# HM10_Breakout.net
KiCad netlist of a schematic drawn in EAGLE
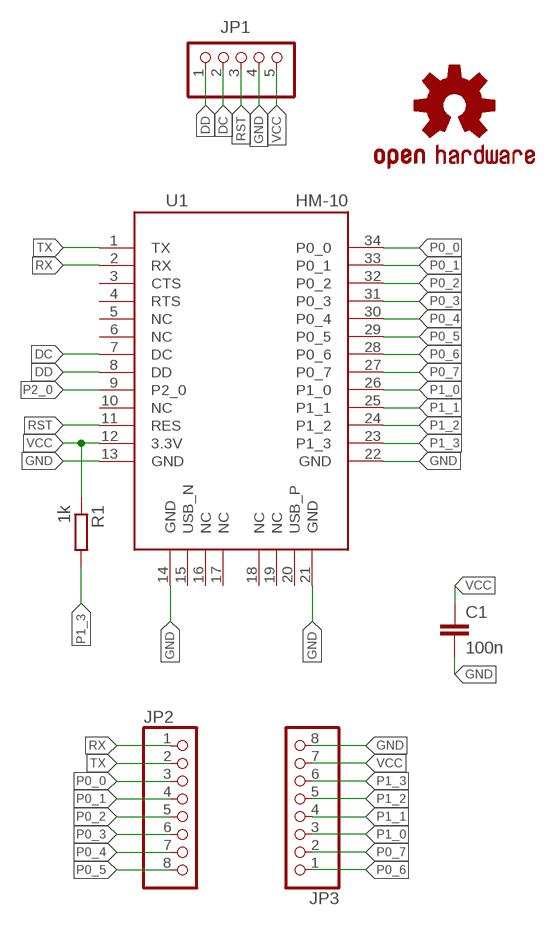
[diagram p0: schematic, sheet 1]

(export (version "E")
  (design (tool "Eeschema 10.0.6"))
  (components
    (comp (ref "C1")
      (value "100n")
      (footprint "eagle-import:1206")
      (libsource (lib "eagle-import") (part "C-EU1206"))
    )
    (comp (ref "JP1")
      (value "PINHD-1X5")
      (footprint "eagle-import:1X05")
      (libsource (lib "eagle-import") (part "PINHD-1X5"))
    )
    (comp (ref "JP2")
      (value "PINHD-1X8")
      (footprint "eagle-import:1X08")
      (libsource (lib "eagle-import") (part "PINHD-1X8"))
    )
    (comp (ref "JP3")
      (value "PINHD-1X8")
      (footprint "eagle-import:1X08")
      (libsource (lib "eagle-import") (part "PINHD-1X8"))
    )
    (comp (ref "LOGO1")
      (value "OSHW-LOGOM")
      (footprint "eagle-import:OSHW-LOGO-M")
      (libsource (lib "eagle-import") (part "OSHW-LOGOM"))
    )
    (comp (ref "R1")
      (value "1k")
      (footprint "eagle-import:R1206")
      (libsource (lib "eagle-import") (part "R-EU_R1206"))
    )
    (comp (ref "U1")
      (value "HM-10")
      (footprint "eagle-import:HM-10")
      (libsource (lib "eagle-import") (part "HM-10"))
    )
  )
  (nets
    (net (code "1") (name "DC") (class "Default")
      (node (ref "JP1") (pin "2") (pinfunction "2_2") (pintype "passive"))
      (node (ref "U1") (pin "7") (pinfunction "DC_7") (pintype "bidirectional"))
    )
    (net (code "2") (name "DD") (class "Default")
      (node (ref "JP1") (pin "1") (pinfunction "1_1") (pintype "passive"))
      (node (ref "U1") (pin "8") (pinfunction "DD_8") (pintype "bidirectional"))
    )
    (net (code "3") (name "GND") (class "Default")
      (node (ref "C1") (pin "2") (pinfunction "2_2") (pintype "passive"))
      (node (ref "JP1") (pin "4") (pinfunction "4_4") (pintype "passive"))
      (node (ref "JP3") (pin "8") (pinfunction "8_8") (pintype "passive"))
      (node (ref "U1") (pin "13") (pinfunction "GND_13") (pintype "bidirectional"))
      (node (ref "U1") (pin "14") (pinfunction "GND_14") (pintype "bidirectional"))
      (node (ref "U1") (pin "21") (pinfunction "GND_21") (pintype "bidirectional"))
      (node (ref "U1") (pin "22") (pinfunction "GND_22") (pintype "bidirectional"))
    )
    (net (code "4") (name "P0_0") (class "Default")
      (node (ref "JP2") (pin "3") (pinfunction "3_3") (pintype "passive"))
      (node (ref "U1") (pin "34") (pinfunction "P0_0_34") (pintype "bidirectional"))
    )
    (net (code "5") (name "P0_1") (class "Default")
      (node (ref "JP2") (pin "4") (pinfunction "4_4") (pintype "passive"))
      (node (ref "U1") (pin "33") (pinfunction "P0_1_33") (pintype "bidirectional"))
    )
    (net (code "6") (name "P0_2") (class "Default")
      (node (ref "JP2") (pin "5") (pinfunction "5_5") (pintype "passive"))
      (node (ref "U1") (pin "32") (pinfunction "P0_2_32") (pintype "bidirectional"))
    )
    (net (code "7") (name "P0_3") (class "Default")
      (node (ref "JP2") (pin "6") (pinfunction "6_6") (pintype "passive"))
      (node (ref "U1") (pin "31") (pinfunction "P0_3_31") (pintype "bidirectional"))
    )
    (net (code "8") (name "P0_4") (class "Default")
      (node (ref "JP2") (pin "7") (pinfunction "7_7") (pintype "passive"))
      (node (ref "U1") (pin "30") (pinfunction "P0_4_30") (pintype "bidirectional"))
    )
    (net (code "9") (name "P0_5") (class "Default")
      (node (ref "JP2") (pin "8") (pinfunction "8_8") (pintype "passive"))
      (node (ref "U1") (pin "29") (pinfunction "P0_5_29") (pintype "bidirectional"))
    )
    (net (code "10") (name "P0_6") (class "Default")
      (node (ref "JP3") (pin "1") (pinfunction "1_1") (pintype "passive"))
      (node (ref "U1") (pin "28") (pinfunction "P0_6_28") (pintype "bidirectional"))
    )
    (net (code "11") (name "P0_7") (class "Default")
      (node (ref "JP3") (pin "2") (pinfunction "2_2") (pintype "passive"))
      (node (ref "U1") (pin "27") (pinfunction "P0_7_27") (pintype "bidirectional"))
    )
    (net (code "12") (name "P1_0") (class "Default")
      (node (ref "JP3") (pin "3") (pinfunction "3_3") (pintype "passive"))
      (node (ref "U1") (pin "26") (pinfunction "P1_0_26") (pintype "bidirectional"))
    )
    (net (code "13") (name "P1_1") (class "Default")
      (node (ref "JP3") (pin "4") (pinfunction "4_4") (pintype "passive"))
      (node (ref "U1") (pin "25") (pinfunction "P1_1_25") (pintype "bidirectional"))
    )
    (net (code "14") (name "P1_2") (class "Default")
      (node (ref "JP3") (pin "5") (pinfunction "5_5") (pintype "passive"))
      (node (ref "U1") (pin "24") (pinfunction "P1_2_24") (pintype "bidirectional"))
    )
    (net (code "15") (name "P1_3") (class "Default")
      (node (ref "JP3") (pin "6") (pinfunction "6_6") (pintype "passive"))
      (node (ref "R1") (pin "2") (pinfunction "2_2") (pintype "passive"))
      (node (ref "U1") (pin "23") (pinfunction "P1_3_23") (pintype "bidirectional"))
    )
    (net (code "16") (name "P2_0") (class "Default")
      (node (ref "U1") (pin "9") (pinfunction "P2_0_9") (pintype "bidirectional"))
    )
    (net (code "17") (name "RST") (class "Default")
      (node (ref "JP1") (pin "3") (pinfunction "3_3") (pintype "passive"))
      (node (ref "U1") (pin "11") (pinfunction "RES_11") (pintype "bidirectional"))
    )
    (net (code "18") (name "RX") (class "Default")
      (node (ref "JP2") (pin "1") (pinfunction "1_1") (pintype "passive"))
      (node (ref "U1") (pin "2") (pinfunction "RX_2") (pintype "bidirectional"))
    )
    (net (code "19") (name "TX") (class "Default")
      (node (ref "JP2") (pin "2") (pinfunction "2_2") (pintype "passive"))
      (node (ref "U1") (pin "1") (pinfunction "TX_1") (pintype "bidirectional"))
    )
    (net (code "20") (name "VCC") (class "Default")
      (node (ref "C1") (pin "1") (pinfunction "1_1") (pintype "passive"))
      (node (ref "JP1") (pin "5") (pinfunction "5_5") (pintype "passive"))
      (node (ref "JP3") (pin "7") (pinfunction "7_7") (pintype "passive"))
      (node (ref "R1") (pin "1") (pinfunction "1_1") (pintype "passive"))
      (node (ref "U1") (pin "12") (pinfunction "3.3V_12") (pintype "bidirectional"))
    )
    (net (code "21") (name "unconnected-(U1-CTS-Pad3)") (class "Default")
      (node (ref "U1") (pin "3") (pinfunction "CTS_3") (pintype "bidirectional"))
    )
    (net (code "22") (name "unconnected-(U1-NC-Pad5)") (class "Default")
      (node (ref "U1") (pin "5") (pinfunction "NC_5") (pintype "bidirectional"))
    )
    (net (code "23") (name "unconnected-(U1-NC-Pad6)") (class "Default")
      (node (ref "U1") (pin "6") (pinfunction "NC_6") (pintype "bidirectional"))
    )
    (net (code "24") (name "unconnected-(U1-NC-Pad10)") (class "Default")
      (node (ref "U1") (pin "10") (pinfunction "NC_10") (pintype "bidirectional"))
    )
    (net (code "25") (name "unconnected-(U1-NC-Pad16)") (class "Default")
      (node (ref "U1") (pin "16") (pinfunction "NC_16") (pintype "bidirectional"))
    )
    (net (code "26") (name "unconnected-(U1-NC-Pad17)") (class "Default")
      (node (ref "U1") (pin "17") (pinfunction "NC_17") (pintype "bidirectional"))
    )
    (net (code "27") (name "unconnected-(U1-NC-Pad18)") (class "Default")
      (node (ref "U1") (pin "18") (pinfunction "NC_18") (pintype "bidirectional"))
    )
    (net (code "28") (name "unconnected-(U1-NC-Pad19)") (class "Default")
      (node (ref "U1") (pin "19") (pinfunction "NC_19") (pintype "bidirectional"))
    )
    (net (code "29") (name "unconnected-(U1-RTS-Pad4)") (class "Default")
      (node (ref "U1") (pin "4") (pinfunction "RTS_4") (pintype "bidirectional"))
    )
    (net (code "30") (name "unconnected-(U1-USB_N-Pad15)") (class "Default")
      (node (ref "U1") (pin "15") (pinfunction "USB_N_15") (pintype "bidirectional"))
    )
    (net (code "31") (name "unconnected-(U1-USB_P-Pad20)") (class "Default")
      (node (ref "U1") (pin "20") (pinfunction "USB_P_20") (pintype "bidirectional"))
    )
  )
)
